# AnalogModule-0_2.net
KiCad netlist of a schematic drawn in EAGLE
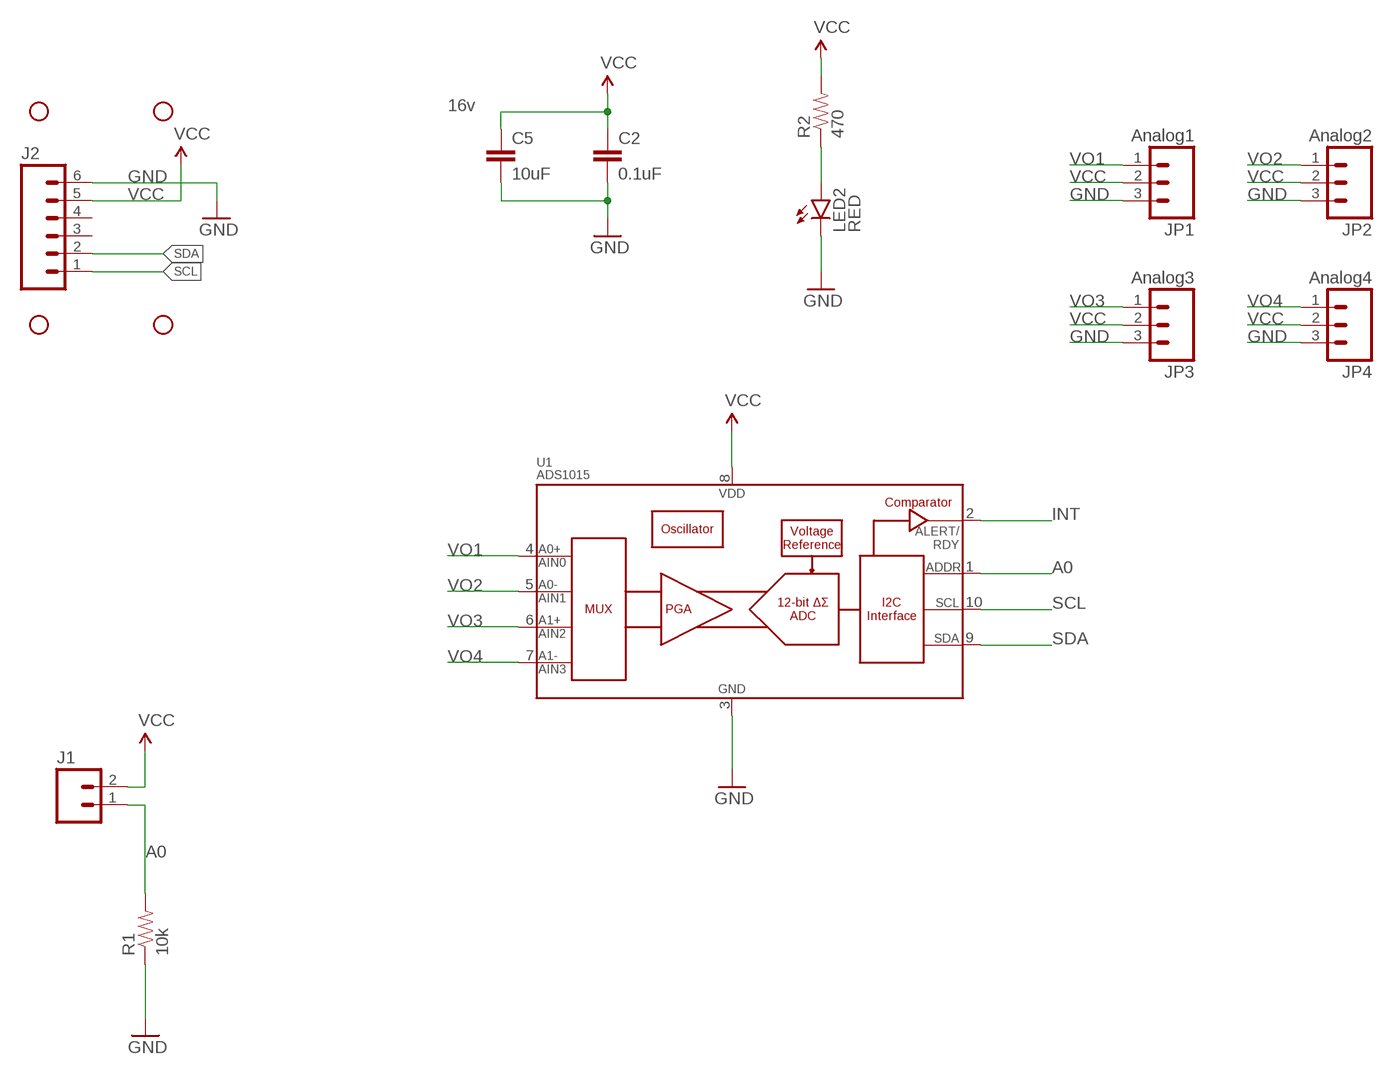
[diagram p0: schematic, sheet 1]

(export (version "E")
  (design (tool "Eeschema 10.0.6"))
  (components
    (comp (ref "C2")
      (value "0.1uF")
      (footprint "eagle-import:0603-CAP")
      (libsource (lib "eagle-import") (part "CAP0603-CAP"))
    )
    (comp (ref "C5")
      (value "10uF")
      (footprint "eagle-import:0805")
      (libsource (lib "eagle-import") (part "CAP0805"))
    )
    (comp (ref "H1")
      (value "STAND-OFFPLATED")
      (footprint "eagle-import:STAND-OFF-PLATED")
      (libsource (lib "eagle-import") (part "STAND-OFFPLATED"))
    )
    (comp (ref "H2")
      (value "STAND-OFFPLATED")
      (footprint "eagle-import:STAND-OFF-PLATED")
      (libsource (lib "eagle-import") (part "STAND-OFFPLATED"))
    )
    (comp (ref "H3")
      (value "STAND-OFFPLATED")
      (footprint "eagle-import:STAND-OFF-PLATED")
      (libsource (lib "eagle-import") (part "STAND-OFFPLATED"))
    )
    (comp (ref "H4")
      (value "STAND-OFFPLATED")
      (footprint "eagle-import:STAND-OFF-PLATED")
      (libsource (lib "eagle-import") (part "STAND-OFFPLATED"))
    )
    (comp (ref "J1")
      (value "M02PTH")
      (footprint "eagle-import:1X02")
      (libsource (lib "eagle-import") (part "M02PTH"))
    )
    (comp (ref "J2")
      (value "M06RJ11")
      (footprint "eagle-import:RJ11-6P6C")
      (libsource (lib "eagle-import") (part "M06RJ11"))
    )
    (comp (ref "JP1")
      (value "Analog1")
      (footprint "eagle-import:JST-3-PTH-VERT")
      (libsource (lib "eagle-import") (part "M03JST-PTH-VERT"))
    )
    (comp (ref "JP2")
      (value "Analog2")
      (footprint "eagle-import:JST-3-PTH-VERT")
      (libsource (lib "eagle-import") (part "M03JST-PTH-VERT"))
    )
    (comp (ref "JP3")
      (value "Analog3")
      (footprint "eagle-import:JST-3-PTH-VERT")
      (libsource (lib "eagle-import") (part "M03JST-PTH-VERT"))
    )
    (comp (ref "JP4")
      (value "Analog4")
      (footprint "eagle-import:JST-3-PTH-VERT")
      (libsource (lib "eagle-import") (part "M03JST-PTH-VERT"))
    )
    (comp (ref "LED2")
      (value "RED")
      (footprint "eagle-import:LED-0603")
      (libsource (lib "eagle-import") (part "LED-RED0603"))
    )
    (comp (ref "R1")
      (value "10k")
      (footprint "eagle-import:0603-RES")
      (libsource (lib "eagle-import") (part "RESISTOR0603"))
    )
    (comp (ref "R2")
      (value "470")
      (footprint "eagle-import:0603-RES")
      (libsource (lib "eagle-import") (part "RESISTOR0603"))
    )
    (comp (ref "U1")
      (value "ADS1015")
      (footprint "eagle-import:MSOP10")
      (libsource (lib "eagle-import") (part "ADS1015"))
    )
  )
  (nets
    (net (code "1") (name "/A0") (class "Default")
      (node (ref "J1") (pin "1") (pinfunction "1_1") (pintype "passive"))
      (node (ref "R1") (pin "2") (pinfunction "2_2") (pintype "passive"))
      (node (ref "U1") (pin "1") (pinfunction "ADDR_1") (pintype "bidirectional"))
    )
    (net (code "2") (name "/INT") (class "Default")
      (node (ref "U1") (pin "2") (pinfunction "ALERT/RDY_2") (pintype "bidirectional"))
    )
    (net (code "3") (name "/VO1") (class "Default")
      (node (ref "JP1") (pin "1") (pinfunction "1_1") (pintype "passive"))
      (node (ref "U1") (pin "4") (pinfunction "AIN0_4") (pintype "bidirectional"))
    )
    (net (code "4") (name "/VO2") (class "Default")
      (node (ref "JP2") (pin "1") (pinfunction "1_1") (pintype "passive"))
      (node (ref "U1") (pin "5") (pinfunction "AIN1_5") (pintype "bidirectional"))
    )
    (net (code "5") (name "/VO3") (class "Default")
      (node (ref "JP3") (pin "1") (pinfunction "1_1") (pintype "passive"))
      (node (ref "U1") (pin "6") (pinfunction "AIN2_6") (pintype "bidirectional"))
    )
    (net (code "6") (name "/VO4") (class "Default")
      (node (ref "JP4") (pin "1") (pinfunction "1_1") (pintype "passive"))
      (node (ref "U1") (pin "7") (pinfunction "AIN3_7") (pintype "bidirectional"))
    )
    (net (code "7") (name "GND") (class "Default")
      (node (ref "C2") (pin "2") (pinfunction "2_2") (pintype "passive"))
      (node (ref "C5") (pin "2") (pinfunction "2_2") (pintype "passive"))
      (node (ref "J2") (pin "6") (pinfunction "6_6") (pintype "passive"))
      (node (ref "JP1") (pin "3") (pinfunction "3_3") (pintype "passive"))
      (node (ref "JP2") (pin "3") (pinfunction "3_3") (pintype "passive"))
      (node (ref "JP3") (pin "3") (pinfunction "3_3") (pintype "passive"))
      (node (ref "JP4") (pin "3") (pinfunction "3_3") (pintype "passive"))
      (node (ref "LED2") (pin "C") (pinfunction "C_C") (pintype "passive"))
      (node (ref "R1") (pin "1") (pinfunction "1_1") (pintype "passive"))
      (node (ref "U1") (pin "3") (pinfunction "VSS_3") (pintype "bidirectional"))
    )
    (net (code "8") (name "Net-(LED2-PadA)") (class "Default")
      (node (ref "LED2") (pin "A") (pinfunction "A_A") (pintype "passive"))
      (node (ref "R2") (pin "1") (pinfunction "1_1") (pintype "passive"))
    )
    (net (code "9") (name "SCL") (class "Default")
      (node (ref "J2") (pin "1") (pinfunction "1_1") (pintype "passive"))
      (node (ref "U1") (pin "10") (pinfunction "SCL_10") (pintype "bidirectional"))
    )
    (net (code "10") (name "SDA") (class "Default")
      (node (ref "J2") (pin "2") (pinfunction "2_2") (pintype "passive"))
      (node (ref "U1") (pin "9") (pinfunction "SDA_9") (pintype "bidirectional"))
    )
    (net (code "11") (name "VCC") (class "Default")
      (node (ref "C2") (pin "1") (pinfunction "1_1") (pintype "passive"))
      (node (ref "C5") (pin "1") (pinfunction "1_1") (pintype "passive"))
      (node (ref "J1") (pin "2") (pinfunction "2_2") (pintype "passive"))
      (node (ref "J2") (pin "5") (pinfunction "5_5") (pintype "passive"))
      (node (ref "JP1") (pin "2") (pinfunction "2_2") (pintype "passive"))
      (node (ref "JP2") (pin "2") (pinfunction "2_2") (pintype "passive"))
      (node (ref "JP3") (pin "2") (pinfunction "2_2") (pintype "passive"))
      (node (ref "JP4") (pin "2") (pinfunction "2_2") (pintype "passive"))
      (node (ref "R2") (pin "2") (pinfunction "2_2") (pintype "passive"))
      (node (ref "U1") (pin "8") (pinfunction "VDD_8") (pintype "bidirectional"))
    )
    (net (code "12") (name "unconnected-(J2-Pad3)") (class "Default")
      (node (ref "J2") (pin "3") (pinfunction "3_3") (pintype "passive"))
    )
    (net (code "13") (name "unconnected-(J2-Pad4)") (class "Default")
      (node (ref "J2") (pin "4") (pinfunction "4_4") (pintype "passive"))
    )
  )
)
